# FPGA.net
KiCad netlist of a schematic drawn in Altium Designer
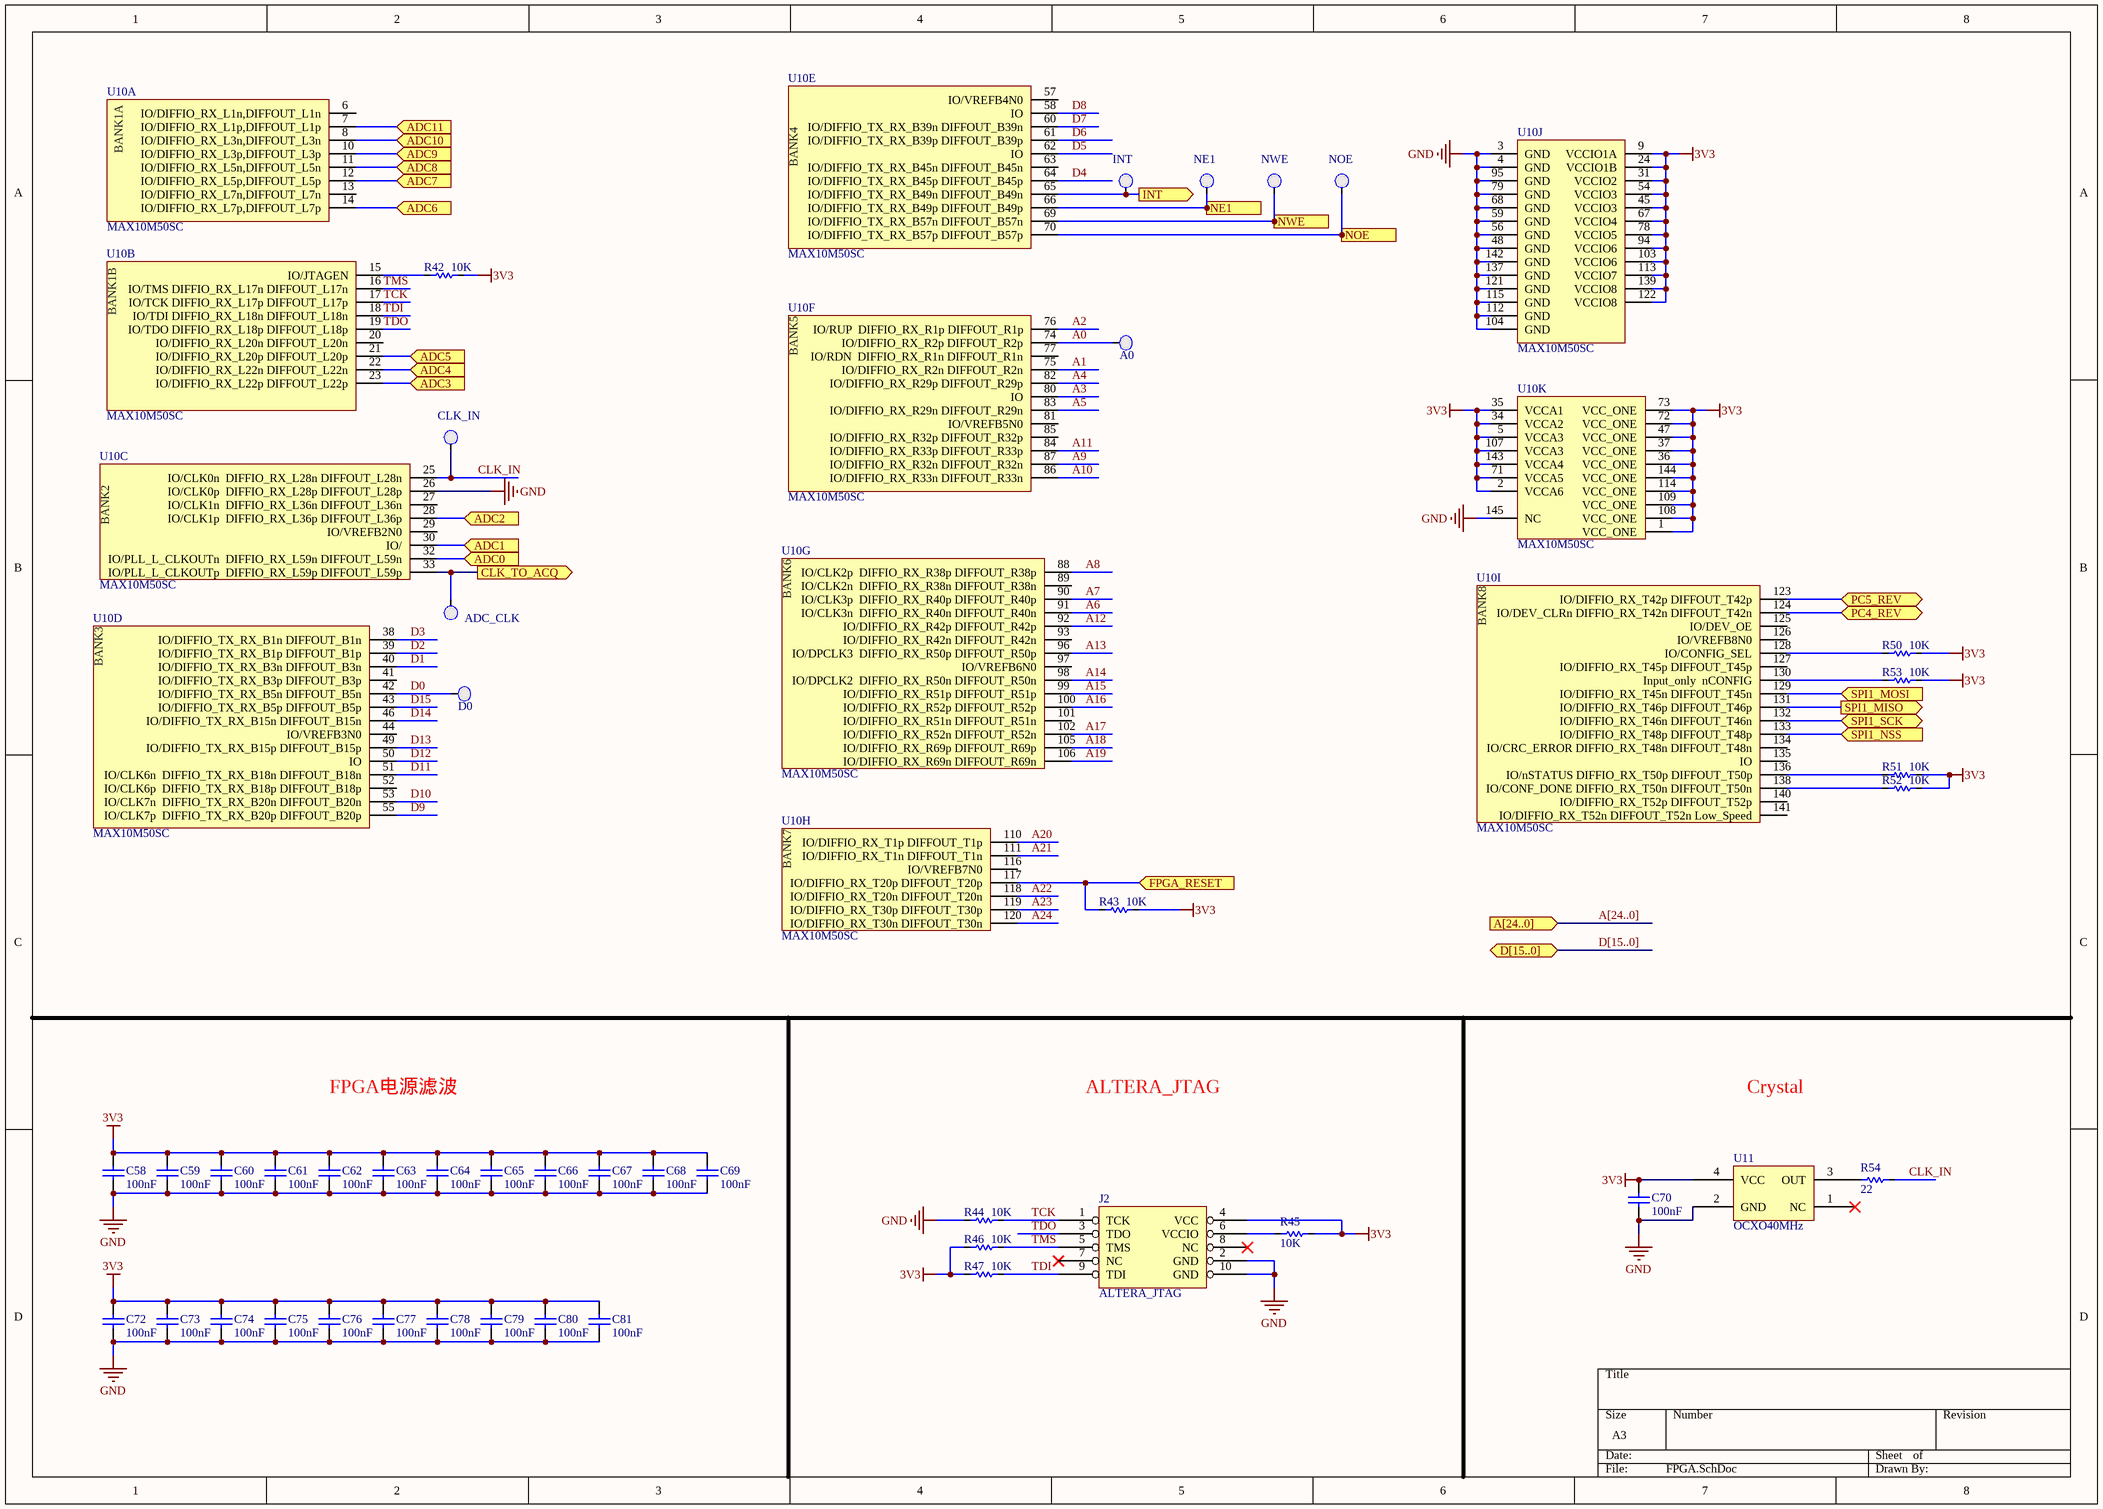
[diagram p0: FPGA.SchDoc]

(export (version "E")
  (design (tool "Eeschema 10.0.6"))
  (components
    (comp (ref "A0") (value "TP") (footprint "TPA") (libsource (lib "") (part "TP_1")))
    (comp (ref "ADC_CLK") (value "TP") (footprint "TPA") (libsource (lib "") (part "TP_2")))
    (comp (ref "C58")
      (value "100nF")
      (footprint "0805C")
      (description "Capacitor")
      (fields (field (name "PUBLISHER") "Altium Limited"))
      (libsource (lib "STM32") (part "Cap"))
    )
    (comp (ref "C59")
      (value "100nF")
      (footprint "0805C")
      (description "Capacitor")
      (fields (field (name "PUBLISHER") "Altium Limited"))
      (libsource (lib "STM32") (part "Cap"))
    )
    (comp (ref "C60")
      (value "100nF")
      (footprint "0805C")
      (description "Capacitor")
      (fields (field (name "PUBLISHER") "Altium Limited"))
      (libsource (lib "STM32") (part "Cap"))
    )
    (comp (ref "C61")
      (value "100nF")
      (footprint "0805C")
      (description "Capacitor")
      (fields (field (name "PUBLISHER") "Altium Limited"))
      (libsource (lib "STM32") (part "Cap"))
    )
    (comp (ref "C62")
      (value "100nF")
      (footprint "0805C")
      (description "Capacitor")
      (fields (field (name "PUBLISHER") "Altium Limited"))
      (libsource (lib "STM32") (part "Cap"))
    )
    (comp (ref "C63")
      (value "100nF")
      (footprint "0805C")
      (description "Capacitor")
      (fields (field (name "PUBLISHER") "Altium Limited"))
      (libsource (lib "STM32") (part "Cap"))
    )
    (comp (ref "C64")
      (value "100nF")
      (footprint "0805C")
      (description "Capacitor")
      (fields (field (name "PUBLISHER") "Altium Limited"))
      (libsource (lib "STM32") (part "Cap"))
    )
    (comp (ref "C65")
      (value "100nF")
      (footprint "0805C")
      (description "Capacitor")
      (fields (field (name "PUBLISHER") "Altium Limited"))
      (libsource (lib "STM32") (part "Cap"))
    )
    (comp (ref "C66")
      (value "100nF")
      (footprint "0805C")
      (description "Capacitor")
      (fields (field (name "PUBLISHER") "Altium Limited"))
      (libsource (lib "STM32") (part "Cap"))
    )
    (comp (ref "C67")
      (value "100nF")
      (footprint "0805C")
      (description "Capacitor")
      (fields (field (name "PUBLISHER") "Altium Limited"))
      (libsource (lib "STM32") (part "Cap"))
    )
    (comp (ref "C68")
      (value "100nF")
      (footprint "0805C")
      (description "Capacitor")
      (fields (field (name "PUBLISHER") "Altium Limited"))
      (libsource (lib "STM32") (part "Cap"))
    )
    (comp (ref "C69")
      (value "100nF")
      (footprint "0805C")
      (description "Capacitor")
      (fields (field (name "PUBLISHER") "Altium Limited"))
      (libsource (lib "STM32") (part "Cap"))
    )
    (comp (ref "C70")
      (value "100nF")
      (footprint "0805C")
      (description "Capacitor")
      (fields (field (name "PUBLISHER") "Altium Limited"))
      (libsource (lib "STM32") (part "Cap"))
    )
    (comp (ref "C72")
      (value "100nF")
      (footprint "0805C")
      (description "Capacitor")
      (fields (field (name "PUBLISHER") "Altium Limited"))
      (libsource (lib "STM32") (part "Cap"))
    )
    (comp (ref "C73")
      (value "100nF")
      (footprint "0805C")
      (description "Capacitor")
      (fields (field (name "PUBLISHER") "Altium Limited"))
      (libsource (lib "STM32") (part "Cap"))
    )
    (comp (ref "C74")
      (value "100nF")
      (footprint "0805C")
      (description "Capacitor")
      (fields (field (name "PUBLISHER") "Altium Limited"))
      (libsource (lib "STM32") (part "Cap"))
    )
    (comp (ref "C75")
      (value "100nF")
      (footprint "0805C")
      (description "Capacitor")
      (fields (field (name "PUBLISHER") "Altium Limited"))
      (libsource (lib "STM32") (part "Cap"))
    )
    (comp (ref "C76")
      (value "100nF")
      (footprint "0805C")
      (description "Capacitor")
      (fields (field (name "PUBLISHER") "Altium Limited"))
      (libsource (lib "STM32") (part "Cap"))
    )
    (comp (ref "C77")
      (value "100nF")
      (footprint "0805C")
      (description "Capacitor")
      (fields (field (name "PUBLISHER") "Altium Limited"))
      (libsource (lib "STM32") (part "Cap"))
    )
    (comp (ref "C78")
      (value "100nF")
      (footprint "0805C")
      (description "Capacitor")
      (fields (field (name "PUBLISHER") "Altium Limited"))
      (libsource (lib "STM32") (part "Cap"))
    )
    (comp (ref "C79")
      (value "100nF")
      (footprint "0805C")
      (description "Capacitor")
      (fields (field (name "PUBLISHER") "Altium Limited"))
      (libsource (lib "STM32") (part "Cap"))
    )
    (comp (ref "C80")
      (value "100nF")
      (footprint "0805C")
      (description "Capacitor")
      (fields (field (name "PUBLISHER") "Altium Limited"))
      (libsource (lib "STM32") (part "Cap"))
    )
    (comp (ref "C81")
      (value "100nF")
      (footprint "0805C")
      (description "Capacitor")
      (fields (field (name "PUBLISHER") "Altium Limited"))
      (libsource (lib "STM32") (part "Cap"))
    )
    (comp (ref "CLK_IN") (value "TP") (footprint "TPA") (libsource (lib "STM32") (part "TP")))
    (comp (ref "D0") (value "TP") (footprint "TPA") (libsource (lib "") (part "TP_1")))
    (comp (ref "INT") (value "TP") (footprint "TPA") (libsource (lib "STM32") (part "TP")))
    (comp (ref "J2")
      (value "ALTERA_JTAG")
      (footprint "JTAG_DIP")
      (libsource (lib "STM32") (part "ALTERA_JTAG"))
    )
    (comp (ref "NE1") (value "TP") (footprint "TPA") (libsource (lib "STM32") (part "TP")))
    (comp (ref "NOE") (value "TP") (footprint "TPA") (libsource (lib "STM32") (part "TP")))
    (comp (ref "NWE") (value "TP") (footprint "TPA") (libsource (lib "STM32") (part "TP")))
    (comp (ref "R42")
      (value "10K")
      (footprint "0805R")
      (description "Resistor")
      (fields (field (name "PUBLISHER") "Altium Limited"))
      (libsource (lib "STM32") (part "Res1"))
    )
    (comp (ref "R43")
      (value "10K")
      (footprint "0805R")
      (description "Resistor")
      (fields (field (name "PUBLISHER") "Altium Limited"))
      (libsource (lib "STM32") (part "Res1"))
    )
    (comp (ref "R44")
      (value "10K")
      (footprint "0805R")
      (description "Resistor")
      (fields (field (name "PUBLISHER") "Altium Limited"))
      (libsource (lib "STM32") (part "Res1"))
    )
    (comp (ref "R45")
      (value "10K")
      (footprint "0805R")
      (description "Resistor")
      (fields (field (name "PUBLISHER") "Altium Limited"))
      (libsource (lib "STM32") (part "Res1"))
    )
    (comp (ref "R46")
      (value "10K")
      (footprint "0805R")
      (description "Resistor")
      (fields (field (name "PUBLISHER") "Altium Limited"))
      (libsource (lib "STM32") (part "Res1"))
    )
    (comp (ref "R47")
      (value "10K")
      (footprint "0805R")
      (description "Resistor")
      (fields (field (name "PUBLISHER") "Altium Limited"))
      (libsource (lib "STM32") (part "Res1"))
    )
    (comp (ref "R50")
      (value "10K")
      (footprint "0805R")
      (description "Resistor")
      (fields (field (name "PUBLISHER") "Altium Limited"))
      (libsource (lib "STM32") (part "Res1"))
    )
    (comp (ref "R51")
      (value "10K")
      (footprint "0805R")
      (description "Resistor")
      (fields (field (name "PUBLISHER") "Altium Limited"))
      (libsource (lib "STM32") (part "Res1"))
    )
    (comp (ref "R52")
      (value "10K")
      (footprint "0805R")
      (description "Resistor")
      (fields (field (name "PUBLISHER") "Altium Limited"))
      (libsource (lib "STM32") (part "Res1"))
    )
    (comp (ref "R53")
      (value "10K")
      (footprint "0805R")
      (description "Resistor")
      (fields (field (name "PUBLISHER") "Altium Limited"))
      (libsource (lib "STM32") (part "Res1"))
    )
    (comp (ref "R54")
      (value "22")
      (footprint "0805R")
      (description "Resistor")
      (fields (field (name "PUBLISHER") "Altium Limited"))
      (libsource (lib "STM32") (part "Res1"))
    )
    (comp (ref "U10")
      (value "MAX10M50SC")
      (footprint "max10M50sc_Quad144")
      (libsource (lib "STM32") (part "MAX10M50SC_144"))
    )
    (comp (ref "U11") (value "OCXO40MHz") (footprint "OCX1") (libsource (lib "STM32") (part "OCXO")))
  )
  (nets
    (net (code "1") (name "/A0") (class "Default")
      (node (ref "A0") (pin "1") (pinfunction "TP_1") (pintype "passive"))
      (node (ref "U10") (pin "74") (pinfunction "IO/DIFFIO_RX_R2p_DIFFOUT_R2p_74") (pintype "passive"))
    )
    (net (code "2") (name "/A1") (class "Default")
      (node (ref "U10") (pin "75") (pinfunction "IO/DIFFIO_RX_R2n_DIFFOUT_R2n_75") (pintype "passive"))
    )
    (net (code "3") (name "/A2") (class "Default")
      (node (ref "U10") (pin "76") (pinfunction "IO/RUP__DIFFIO_RX_R1p_DIFFOUT_R1p_76") (pintype "passive"))
    )
    (net (code "4") (name "/A3") (class "Default")
      (node (ref "U10") (pin "80") (pinfunction "IO_80") (pintype "passive"))
    )
    (net (code "5") (name "/A4") (class "Default")
      (node (ref "U10") (pin "82") (pinfunction "IO/DIFFIO_RX_R29p_DIFFOUT_R29p_82") (pintype "passive"))
    )
    (net (code "6") (name "/A5") (class "Default")
      (node (ref "U10") (pin "83") (pinfunction "IO/DIFFIO_RX_R29n_DIFFOUT_R29n_83") (pintype "passive"))
    )
    (net (code "7") (name "/A6") (class "Default")
      (node (ref "U10") (pin "91") (pinfunction "IO/CLK3n__DIFFIO_RX_R40n_DIFFOUT_R40n_91") (pintype "passive"))
    )
    (net (code "8") (name "/A7") (class "Default")
      (node (ref "U10") (pin "90") (pinfunction "IO/CLK3p__DIFFIO_RX_R40p_DIFFOUT_R40p_90") (pintype "passive"))
    )
    (net (code "9") (name "/A8") (class "Default")
      (node (ref "U10") (pin "88") (pinfunction "IO/CLK2p__DIFFIO_RX_R38p_DIFFOUT_R38p_88") (pintype "passive"))
    )
    (net (code "10") (name "/A9") (class "Default")
      (node (ref "U10") (pin "87") (pinfunction "IO/DIFFIO_RX_R32n_DIFFOUT_R32n_87") (pintype "passive"))
    )
    (net (code "11") (name "/A10") (class "Default")
      (node (ref "U10") (pin "86") (pinfunction "IO/DIFFIO_RX_R33n_DIFFOUT_R33n_86") (pintype "passive"))
    )
    (net (code "12") (name "/A11") (class "Default")
      (node (ref "U10") (pin "84") (pinfunction "IO/DIFFIO_RX_R33p_DIFFOUT_R33p_84") (pintype "passive"))
    )
    (net (code "13") (name "/A12") (class "Default")
      (node (ref "U10") (pin "92") (pinfunction "IO/DIFFIO_RX_R42p_DIFFOUT_R42p_92") (pintype "passive"))
    )
    (net (code "14") (name "/A13") (class "Default")
      (node (ref "U10") (pin "96") (pinfunction "IO/DPCLK3__DIFFIO_RX_R50p_DIFFOUT_R50p_96") (pintype "passive"))
    )
    (net (code "15") (name "/A14") (class "Default")
      (node (ref "U10") (pin "98") (pinfunction "IO/DPCLK2__DIFFIO_RX_R50n_DIFFOUT_R50n_98") (pintype "passive"))
    )
    (net (code "16") (name "/A15") (class "Default")
      (node (ref "U10") (pin "99") (pinfunction "IO/DIFFIO_RX_R51p_DIFFOUT_R51p_99") (pintype "passive"))
    )
    (net (code "17") (name "/A16") (class "Default")
      (node (ref "U10") (pin "100") (pinfunction "IO/DIFFIO_RX_R52p_DIFFOUT_R52p_100") (pintype "passive"))
    )
    (net (code "18") (name "/A17") (class "Default")
      (node (ref "U10") (pin "102") (pinfunction "IO/DIFFIO_RX_R52n_DIFFOUT_R52n_102") (pintype "passive"))
    )
    (net (code "19") (name "/A18") (class "Default")
      (node (ref "U10") (pin "105") (pinfunction "IO/DIFFIO_RX_R69p_DIFFOUT_R69p_105") (pintype "passive"))
    )
    (net (code "20") (name "/A19") (class "Default")
      (node (ref "U10") (pin "106") (pinfunction "IO/DIFFIO_RX_R69n_DIFFOUT_R69n_106") (pintype "passive"))
    )
    (net (code "21") (name "/A20") (class "Default")
      (node (ref "U10") (pin "110") (pinfunction "IO/DIFFIO_RX_T1p_DIFFOUT_T1p_110") (pintype "passive"))
    )
    (net (code "22") (name "/A21") (class "Default")
      (node (ref "U10") (pin "111") (pinfunction "IO/DIFFIO_RX_T1n_DIFFOUT_T1n_111") (pintype "passive"))
    )
    (net (code "23") (name "/A22") (class "Default")
      (node (ref "U10") (pin "118") (pinfunction "IO/DIFFIO_RX_T20n_DIFFOUT_T20n_118") (pintype "passive"))
    )
    (net (code "24") (name "/A23") (class "Default")
      (node (ref "U10") (pin "119") (pinfunction "IO/DIFFIO_RX_T30p_DIFFOUT_T30p_119") (pintype "passive"))
    )
    (net (code "25") (name "/A24") (class "Default")
      (node (ref "U10") (pin "120") (pinfunction "IO/DIFFIO_RX_T30n_DIFFOUT_T30n_120") (pintype "passive"))
    )
    (net (code "26") (name "/ADC0") (class "Default")
      (node (ref "U10") (pin "32") (pinfunction "IO/PLL_L_CLKOUTn__DIFFIO_RX_L59n_DIFFOUT_L59n_32") (pintype "passive"))
    )
    (net (code "27") (name "/ADC1") (class "Default")
      (node (ref "U10") (pin "30") (pinfunction "IO/_30") (pintype "passive"))
    )
    (net (code "28") (name "/ADC2") (class "Default")
      (node (ref "U10") (pin "28") (pinfunction "IO/CLK1p__DIFFIO_RX_L36p_DIFFOUT_L36p_28") (pintype "passive"))
    )
    (net (code "29") (name "/ADC3") (class "Default")
      (node (ref "U10") (pin "23") (pinfunction "IO/DIFFIO_RX_L22p_DIFFOUT_L22p_23") (pintype "passive"))
    )
    (net (code "30") (name "/ADC4") (class "Default")
      (node (ref "U10") (pin "22") (pinfunction "IO/DIFFIO_RX_L22n_DIFFOUT_L22n_22") (pintype "passive"))
    )
    (net (code "31") (name "/ADC5") (class "Default")
      (node (ref "U10") (pin "21") (pinfunction "IO/DIFFIO_RX_L20p_DIFFOUT_L20p_21") (pintype "passive"))
    )
    (net (code "32") (name "/ADC6") (class "Default")
      (node (ref "U10") (pin "14") (pinfunction "IO/DIFFIO_RX_L7p,DIFFOUT_L7p_14") (pintype "passive"))
    )
    (net (code "33") (name "/ADC7") (class "Default")
      (node (ref "U10") (pin "12") (pinfunction "IO/DIFFIO_RX_L5p,DIFFOUT_L5p_12") (pintype "passive"))
    )
    (net (code "34") (name "/ADC8") (class "Default")
      (node (ref "U10") (pin "11") (pinfunction "IO/DIFFIO_RX_L5n,DIFFOUT_L5n_11") (pintype "passive"))
    )
    (net (code "35") (name "/ADC9") (class "Default")
      (node (ref "U10") (pin "10") (pinfunction "IO/DIFFIO_RX_L3p,DIFFOUT_L3p_10") (pintype "passive"))
    )
    (net (code "36") (name "/ADC10") (class "Default")
      (node (ref "U10") (pin "8") (pinfunction "IO/DIFFIO_RX_L3n,DIFFOUT_L3n_8") (pintype "passive"))
    )
    (net (code "37") (name "/ADC11") (class "Default")
      (node (ref "U10") (pin "7") (pinfunction "IO/DIFFIO_RX_L1p,DIFFOUT_L1p_7") (pintype "passive"))
    )
    (net (code "39") (name "/CLK_IN") (class "Default")
      (node (ref "CLK_IN") (pin "1") (pinfunction "TP_1") (pintype "passive"))
      (node (ref "R54") (pin "2") (pinfunction "2_2") (pintype "passive"))
      (node (ref "U10") (pin "25") (pinfunction "IO/CLK0n__DIFFIO_RX_L28n_DIFFOUT_L28n_25") (pintype "passive"))
    )
    (net (code "40") (name "/CLK_TO_ACQ") (class "Default")
      (node (ref "ADC_CLK") (pin "1") (pinfunction "TP_1") (pintype "passive"))
      (node (ref "U10") (pin "33") (pinfunction "IO/PLL_L_CLKOUTp__DIFFIO_RX_L59p_DIFFOUT_L59p_33") (pintype "passive"))
    )
    (net (code "41") (name "/D0") (class "Default")
      (node (ref "D0") (pin "1") (pinfunction "TP_1") (pintype "passive"))
      (node (ref "U10") (pin "42") (pinfunction "IO/DIFFIO_TX_RX_B5n_DIFFOUT_B5n_42") (pintype "passive"))
    )
    (net (code "42") (name "/D1") (class "Default")
      (node (ref "U10") (pin "40") (pinfunction "IO/DIFFIO_TX_RX_B3n_DIFFOUT_B3n_40") (pintype "passive"))
    )
    (net (code "43") (name "/D2") (class "Default")
      (node (ref "U10") (pin "39") (pinfunction "IO/DIFFIO_TX_RX_B1p_DIFFOUT_B1p_39") (pintype "passive"))
    )
    (net (code "44") (name "/D3") (class "Default")
      (node (ref "U10") (pin "38") (pinfunction "IO/DIFFIO_TX_RX_B1n_DIFFOUT_B1n_38") (pintype "passive"))
    )
    (net (code "45") (name "/D4") (class "Default")
      (node (ref "U10") (pin "64") (pinfunction "IO/DIFFIO_TX_RX_B45p_DIFFOUT_B45p_64") (pintype "passive"))
    )
    (net (code "46") (name "/D5") (class "Default")
      (node (ref "U10") (pin "62") (pinfunction "IO_62") (pintype "passive"))
    )
    (net (code "47") (name "/D6") (class "Default")
      (node (ref "U10") (pin "61") (pinfunction "IO/DIFFIO_TX_RX_B39p_DIFFOUT_B39p_61") (pintype "passive"))
    )
    (net (code "48") (name "/D7") (class "Default")
      (node (ref "U10") (pin "60") (pinfunction "IO/DIFFIO_TX_RX_B39n_DIFFOUT_B39n_60") (pintype "passive"))
    )
    (net (code "49") (name "/D8") (class "Default")
      (node (ref "U10") (pin "58") (pinfunction "IO_58") (pintype "passive"))
    )
    (net (code "50") (name "/D9") (class "Default")
      (node (ref "U10") (pin "55") (pinfunction "IO/CLK7p__DIFFIO_TX_RX_B20p_DIFFOUT_B20p_55") (pintype "passive"))
    )
    (net (code "51") (name "/D10") (class "Default")
      (node (ref "U10") (pin "53") (pinfunction "IO/CLK7n__DIFFIO_TX_RX_B20n_DIFFOUT_B20n_53") (pintype "passive"))
    )
    (net (code "52") (name "/D11") (class "Default")
      (node (ref "U10") (pin "51") (pinfunction "IO/CLK6n__DIFFIO_TX_RX_B18n_DIFFOUT_B18n_51") (pintype "passive"))
    )
    (net (code "53") (name "/D12") (class "Default")
      (node (ref "U10") (pin "50") (pinfunction "IO_50") (pintype "passive"))
    )
    (net (code "54") (name "/D13") (class "Default")
      (node (ref "U10") (pin "49") (pinfunction "IO/DIFFIO_TX_RX_B15p_DIFFOUT_B15p_49") (pintype "passive"))
    )
    (net (code "55") (name "/D14") (class "Default")
      (node (ref "U10") (pin "46") (pinfunction "IO/DIFFIO_TX_RX_B15n_DIFFOUT_B15n_46") (pintype "passive"))
    )
    (net (code "56") (name "/D15") (class "Default")
      (node (ref "U10") (pin "43") (pinfunction "IO/DIFFIO_TX_RX_B5p_DIFFOUT_B5p_43") (pintype "passive"))
    )
    (net (code "58") (name "/FPGA_RESET") (class "Default")
      (node (ref "R43") (pin "1") (pinfunction "1_1") (pintype "passive"))
      (node (ref "U10") (pin "117") (pinfunction "IO/DIFFIO_RX_T20p_DIFFOUT_T20p_117") (pintype "passive"))
    )
    (net (code "59") (name "/INT") (class "Default")
      (node (ref "INT") (pin "1") (pinfunction "TP_1") (pintype "passive"))
      (node (ref "U10") (pin "65") (pinfunction "IO/DIFFIO_TX_RX_B49n_DIFFOUT_B49n_65") (pintype "passive"))
    )
    (net (code "60") (name "/NE1") (class "Default")
      (node (ref "NE1") (pin "1") (pinfunction "TP_1") (pintype "passive"))
      (node (ref "U10") (pin "66") (pinfunction "IO/DIFFIO_TX_RX_B49p_DIFFOUT_B49p_66") (pintype "passive"))
    )
    (net (code "61") (name "/NOE") (class "Default")
      (node (ref "NOE") (pin "1") (pinfunction "TP_1") (pintype "passive"))
      (node (ref "U10") (pin "70") (pinfunction "IO/DIFFIO_TX_RX_B57p_DIFFOUT_B57p_70") (pintype "passive"))
    )
    (net (code "62") (name "/NWE") (class "Default")
      (node (ref "NWE") (pin "1") (pinfunction "TP_1") (pintype "passive"))
      (node (ref "U10") (pin "69") (pinfunction "IO/DIFFIO_TX_RX_B57n_DIFFOUT_B57n_69") (pintype "passive"))
    )
    (net (code "63") (name "/PC4_REV") (class "Default")
      (node (ref "U10") (pin "124") (pinfunction "IO/DEV_CLRn_DIFFIO_RX_T42n_DIFFOUT_T42n_124") (pintype "passive"))
    )
    (net (code "64") (name "/PC5_REV") (class "Default")
      (node (ref "U10") (pin "123") (pinfunction "IO/DIFFIO_RX_T42p_DIFFOUT_T42p_123") (pintype "passive"))
    )
    (net (code "65") (name "/SPI1_MISO") (class "Default")
      (node (ref "U10") (pin "131") (pinfunction "IO/DIFFIO_RX_T46p_DIFFOUT_T46p_131") (pintype "passive"))
    )
    (net (code "66") (name "/SPI1_MOSI") (class "Default")
      (node (ref "U10") (pin "129") (pinfunction "IO/DIFFIO_RX_T45n_DIFFOUT_T45n_129") (pintype "passive"))
    )
    (net (code "67") (name "/SPI1_NSS") (class "Default")
      (node (ref "U10") (pin "133") (pinfunction "IO/DIFFIO_RX_T48p_DIFFOUT_T48p_133") (pintype "passive"))
    )
    (net (code "68") (name "/SPI1_SCK") (class "Default")
      (node (ref "U10") (pin "132") (pinfunction "IO/DIFFIO_RX_T46n_DIFFOUT_T46n_132") (pintype "passive"))
    )
    (net (code "69") (name "/TCK") (class "Default")
      (node (ref "J2") (pin "1") (pinfunction "TCK_1") (pintype "passive"))
      (node (ref "R44") (pin "2") (pinfunction "2_2") (pintype "passive"))
      (node (ref "U10") (pin "17") (pinfunction "IO/TCK_DIFFIO_RX_L17p_DIFFOUT_L17p_17") (pintype "passive"))
    )
    (net (code "70") (name "/TDI") (class "Default")
      (node (ref "J2") (pin "9") (pinfunction "TDI_9") (pintype "passive"))
      (node (ref "R47") (pin "2") (pinfunction "2_2") (pintype "passive"))
      (node (ref "U10") (pin "18") (pinfunction "IO/TDI_DIFFIO_RX_L18n_DIFFOUT_L18n_18") (pintype "passive"))
    )
    (net (code "71") (name "/TDO") (class "Default")
      (node (ref "J2") (pin "3") (pinfunction "TDO_3") (pintype "passive"))
      (node (ref "U10") (pin "19") (pinfunction "IO/TDO_DIFFIO_RX_L18p_DIFFOUT_L18p_19") (pintype "passive"))
    )
    (net (code "72") (name "/TMS") (class "Default")
      (node (ref "J2") (pin "5") (pinfunction "TMS_5") (pintype "passive"))
      (node (ref "R46") (pin "2") (pinfunction "2_2") (pintype "passive"))
      (node (ref "U10") (pin "16") (pinfunction "IO/TMS_DIFFIO_RX_L17n_DIFFOUT_L17n_16") (pintype "passive"))
    )
    (net (code "73") (name "3V3") (class "Default")
      (node (ref "C58") (pin "2") (pinfunction "2_2") (pintype "passive"))
      (node (ref "C59") (pin "2") (pinfunction "2_2") (pintype "passive"))
      (node (ref "C60") (pin "2") (pinfunction "2_2") (pintype "passive"))
      (node (ref "C61") (pin "2") (pinfunction "2_2") (pintype "passive"))
      (node (ref "C62") (pin "2") (pinfunction "2_2") (pintype "passive"))
      (node (ref "C63") (pin "2") (pinfunction "2_2") (pintype "passive"))
      (node (ref "C64") (pin "2") (pinfunction "2_2") (pintype "passive"))
      (node (ref "C65") (pin "2") (pinfunction "2_2") (pintype "passive"))
      (node (ref "C66") (pin "2") (pinfunction "2_2") (pintype "passive"))
      (node (ref "C67") (pin "2") (pinfunction "2_2") (pintype "passive"))
      (node (ref "C68") (pin "2") (pinfunction "2_2") (pintype "passive"))
      (node (ref "C69") (pin "2") (pinfunction "2_2") (pintype "passive"))
      (node (ref "C70") (pin "2") (pinfunction "2_2") (pintype "passive"))
      (node (ref "C72") (pin "2") (pinfunction "2_2") (pintype "passive"))
      (node (ref "C73") (pin "2") (pinfunction "2_2") (pintype "passive"))
      (node (ref "C74") (pin "2") (pinfunction "2_2") (pintype "passive"))
      (node (ref "C75") (pin "2") (pinfunction "2_2") (pintype "passive"))
      (node (ref "C76") (pin "2") (pinfunction "2_2") (pintype "passive"))
      (node (ref "C77") (pin "2") (pinfunction "2_2") (pintype "passive"))
      (node (ref "C78") (pin "2") (pinfunction "2_2") (pintype "passive"))
      (node (ref "C79") (pin "2") (pinfunction "2_2") (pintype "passive"))
      (node (ref "C80") (pin "2") (pinfunction "2_2") (pintype "passive"))
      (node (ref "C81") (pin "2") (pinfunction "2_2") (pintype "passive"))
      (node (ref "J2") (pin "4") (pinfunction "VCC_4") (pintype "passive"))
      (node (ref "R42") (pin "2") (pinfunction "2_2") (pintype "passive"))
      (node (ref "R43") (pin "2") (pinfunction "2_2") (pintype "passive"))
      (node (ref "R45") (pin "2") (pinfunction "2_2") (pintype "passive"))
      (node (ref "R46") (pin "1") (pinfunction "1_1") (pintype "passive"))
      (node (ref "R47") (pin "1") (pinfunction "1_1") (pintype "passive"))
      (node (ref "R50") (pin "2") (pinfunction "2_2") (pintype "passive"))
      (node (ref "R51") (pin "2") (pinfunction "2_2") (pintype "passive"))
      (node (ref "R52") (pin "2") (pinfunction "2_2") (pintype "passive"))
      (node (ref "R53") (pin "2") (pinfunction "2_2") (pintype "passive"))
      (node (ref "U10") (pin "1") (pinfunction "VCC_ONE_1") (pintype "passive"))
      (node (ref "U10") (pin "103") (pinfunction "VCCIO6_103") (pintype "passive"))
      (node (ref "U10") (pin "107") (pinfunction "VCCA3_107") (pintype "passive"))
      (node (ref "U10") (pin "108") (pinfunction "VCC_ONE_108") (pintype "passive"))
      (node (ref "U10") (pin "109") (pinfunction "VCC_ONE_109") (pintype "passive"))
      (node (ref "U10") (pin "113") (pinfunction "VCCIO7_113") (pintype "passive"))
      (node (ref "U10") (pin "114") (pinfunction "VCC_ONE_114") (pintype "passive"))
      (node (ref "U10") (pin "122") (pinfunction "VCCIO8_122") (pintype "passive"))
      (node (ref "U10") (pin "139") (pinfunction "VCCIO8_139") (pintype "passive"))
      (node (ref "U10") (pin "143") (pinfunction "VCCA4_143") (pintype "passive"))
      (node (ref "U10") (pin "144") (pinfunction "VCC_ONE_144") (pintype "passive"))
      (node (ref "U10") (pin "2") (pinfunction "VCCA6_2") (pintype "passive"))
      (node (ref "U10") (pin "24") (pinfunction "VCCIO1B_24") (pintype "passive"))
      (node (ref "U10") (pin "31") (pinfunction "VCCIO2_31") (pintype "passive"))
      (node (ref "U10") (pin "34") (pinfunction "VCCA2_34") (pintype "passive"))
      (node (ref "U10") (pin "35") (pinfunction "VCCA1_35") (pintype "passive"))
      (node (ref "U10") (pin "36") (pinfunction "VCC_ONE_36") (pintype "passive"))
      (node (ref "U10") (pin "37") (pinfunction "VCC_ONE_37") (pintype "passive"))
      (node (ref "U10") (pin "45") (pinfunction "VCCIO3_45") (pintype "passive"))
      (node (ref "U10") (pin "47") (pinfunction "VCC_ONE_47") (pintype "passive"))
      (node (ref "U10") (pin "5") (pinfunction "VCCA3_5") (pintype "passive"))
      (node (ref "U10") (pin "54") (pinfunction "VCCIO3_54") (pintype "passive"))
      (node (ref "U10") (pin "67") (pinfunction "VCCIO4_67") (pintype "passive"))
      (node (ref "U10") (pin "71") (pinfunction "VCCA5_71") (pintype "passive"))
      (node (ref "U10") (pin "72") (pinfunction "VCC_ONE_72") (pintype "passive"))
      (node (ref "U10") (pin "73") (pinfunction "VCC_ONE_73") (pintype "passive"))
      (node (ref "U10") (pin "78") (pinfunction "VCCIO5_78") (pintype "passive"))
      (node (ref "U10") (pin "9") (pinfunction "VCCIO1A_9") (pintype "passive"))
      (node (ref "U10") (pin "94") (pinfunction "VCCIO6_94") (pintype "passive"))
      (node (ref "U11") (pin "4") (pinfunction "VCC_4") (pintype "passive"))
    )
    (net (code "74") (name "GND") (class "Default")
      (node (ref "C58") (pin "1") (pinfunction "1_1") (pintype "passive"))
      (node (ref "C59") (pin "1") (pinfunction "1_1") (pintype "passive"))
      (node (ref "C60") (pin "1") (pinfunction "1_1") (pintype "passive"))
      (node (ref "C61") (pin "1") (pinfunction "1_1") (pintype "passive"))
      (node (ref "C62") (pin "1") (pinfunction "1_1") (pintype "passive"))
      (node (ref "C63") (pin "1") (pinfunction "1_1") (pintype "passive"))
      (node (ref "C64") (pin "1") (pinfunction "1_1") (pintype "passive"))
      (node (ref "C65") (pin "1") (pinfunction "1_1") (pintype "passive"))
      (node (ref "C66") (pin "1") (pinfunction "1_1") (pintype "passive"))
      (node (ref "C67") (pin "1") (pinfunction "1_1") (pintype "passive"))
      (node (ref "C68") (pin "1") (pinfunction "1_1") (pintype "passive"))
      (node (ref "C69") (pin "1") (pinfunction "1_1") (pintype "passive"))
      (node (ref "C70") (pin "1") (pinfunction "1_1") (pintype "passive"))
      (node (ref "C72") (pin "1") (pinfunction "1_1") (pintype "passive"))
      (node (ref "C73") (pin "1") (pinfunction "1_1") (pintype "passive"))
      (node (ref "C74") (pin "1") (pinfunction "1_1") (pintype "passive"))
      (node (ref "C75") (pin "1") (pinfunction "1_1") (pintype "passive"))
      (node (ref "C76") (pin "1") (pinfunction "1_1") (pintype "passive"))
      (node (ref "C77") (pin "1") (pinfunction "1_1") (pintype "passive"))
      (node (ref "C78") (pin "1") (pinfunction "1_1") (pintype "passive"))
      (node (ref "C79") (pin "1") (pinfunction "1_1") (pintype "passive"))
      (node (ref "C80") (pin "1") (pinfunction "1_1") (pintype "passive"))
      (node (ref "C81") (pin "1") (pinfunction "1_1") (pintype "passive"))
      (node (ref "J2") (pin "10") (pinfunction "GND_10") (pintype "passive"))
      (node (ref "J2") (pin "2") (pinfunction "GND_2") (pintype "passive"))
      (node (ref "R44") (pin "1") (pinfunction "1_1") (pintype "passive"))
      (node (ref "U10") (pin "104") (pinfunction "GND_104") (pintype "passive"))
      (node (ref "U10") (pin "112") (pinfunction "GND_112") (pintype "passive"))
      (node (ref "U10") (pin "115") (pinfunction "GND_115") (pintype "passive"))
      (node (ref "U10") (pin "121") (pinfunction "GND_121") (pintype "passive"))
      (node (ref "U10") (pin "137") (pinfunction "GND_137") (pintype "passive"))
      (node (ref "U10") (pin "142") (pinfunction "GND_142") (pintype "passive"))
      (node (ref "U10") (pin "145") (pinfunction "NC_145") (pintype "passive"))
      (node (ref "U10") (pin "26") (pinfunction "IO/CLK0p__DIFFIO_RX_L28p_DIFFOUT_L28p_26") (pintype "passive"))
      (node (ref "U10") (pin "3") (pinfunction "GND_3") (pintype "passive"))
      (node (ref "U10") (pin "4") (pinfunction "GND_4") (pintype "passive"))
      (node (ref "U10") (pin "48") (pinfunction "GND_48") (pintype "passive"))
      (node (ref "U10") (pin "56") (pinfunction "GND_56") (pintype "passive"))
      (node (ref "U10") (pin "59") (pinfunction "GND_59") (pintype "passive"))
      (node (ref "U10") (pin "68") (pinfunction "GND_68") (pintype "passive"))
      (node (ref "U10") (pin "79") (pinfunction "GND_79") (pintype "passive"))
      (node (ref "U10") (pin "95") (pinfunction "GND_95") (pintype "passive"))
      (node (ref "U11") (pin "2") (pinfunction "GND_2") (pintype "passive"))
    )
    (net (code "75") (name "Net-(J2-VCCIO)") (class "Default")
      (node (ref "J2") (pin "6") (pinfunction "VCCIO_6") (pintype "passive"))
      (node (ref "R45") (pin "1") (pinfunction "1_1") (pintype "passive"))
    )
    (net (code "76") (name "Net-(U10B-IO{slash}JTAGEN)") (class "Default")
      (node (ref "R42") (pin "1") (pinfunction "1_1") (pintype "passive"))
      (node (ref "U10") (pin "15") (pinfunction "IO/JTAGEN_15") (pintype "passive"))
    )
    (net (code "77") (name "Net-(U10I-IO{slash}CONFIG_SEL)") (class "Default")
      (node (ref "R50") (pin "1") (pinfunction "1_1") (pintype "passive"))
      (node (ref "U10") (pin "128") (pinfunction "IO/CONFIG_SEL_128") (pintype "passive"))
    )
    (net (code "78") (name "Net-(U10I-IO{slash}CONF_DONE_DIFFIO_RX_T50n_DIFFOUT_T50n)") (class "Default")
      (node (ref "R52") (pin "1") (pinfunction "1_1") (pintype "passive"))
      (node (ref "U10") (pin "138") (pinfunction "IO/CONF_DONE_DIFFIO_RX_T50n_DIFFOUT_T50n_138") (pintype "passive"))
    )
    (net (code "79") (name "Net-(U10I-IO{slash}nSTATUS_DIFFIO_RX_T50p_DIFFOUT_T50p)") (class "Default")
      (node (ref "R51") (pin "1") (pinfunction "1_1") (pintype "passive"))
      (node (ref "U10") (pin "136") (pinfunction "IO/nSTATUS_DIFFIO_RX_T50p_DIFFOUT_T50p_136") (pintype "passive"))
    )
    (net (code "80") (name "Net-(U10I-Input_only__nCONFIG)") (class "Default")
      (node (ref "R53") (pin "1") (pinfunction "1_1") (pintype "passive"))
      (node (ref "U10") (pin "130") (pinfunction "Input_only__nCONFIG_130") (pintype "passive"))
    )
    (net (code "81") (name "Net-(U11-OUT)") (class "Default")
      (node (ref "R54") (pin "1") (pinfunction "1_1") (pintype "passive"))
      (node (ref "U11") (pin "3") (pinfunction "OUT_3") (pintype "passive"))
    )
    (net (code "82") (name "unconnected-(J2-NC-Pad7)") (class "Default")
      (node (ref "J2") (pin "7") (pinfunction "NC_7") (pintype "passive+no_connect"))
    )
    (net (code "83") (name "unconnected-(J2-NC-Pad8)") (class "Default")
      (node (ref "J2") (pin "8") (pinfunction "NC_8") (pintype "passive+no_connect"))
    )
    (net (code "84") (name "unconnected-(U10A-IO{slash}DIFFIO_RX_L1n,DIFFOUT_L1n-Pad6)") (class "Default")
      (node (ref "U10") (pin "6") (pinfunction "IO/DIFFIO_RX_L1n,DIFFOUT_L1n_6") (pintype "passive"))
    )
    (net (code "85") (name "unconnected-(U10A-IO{slash}DIFFIO_RX_L7n,DIFFOUT_L7n-Pad13)") (class "Default")
      (node (ref "U10") (pin "13") (pinfunction "IO/DIFFIO_RX_L7n,DIFFOUT_L7n_13") (pintype "passive"))
    )
    (net (code "86") (name "unconnected-(U10B-IO{slash}DIFFIO_RX_L20n_DIFFOUT_L20n-Pad20)") (class "Default")
      (node (ref "U10") (pin "20") (pinfunction "IO/DIFFIO_RX_L20n_DIFFOUT_L20n_20") (pintype "passive"))
    )
    (net (code "87") (name "unconnected-(U10C-IO{slash}CLK1n__DIFFIO_RX_L36n_DIFFOUT_L36n-Pad27)") (class "Default")
      (node (ref "U10") (pin "27") (pinfunction "IO/CLK1n__DIFFIO_RX_L36n_DIFFOUT_L36n_27") (pintype "passive"))
    )
    (net (code "88") (name "unconnected-(U10C-IO{slash}VREFB2N0-Pad29)") (class "Default")
      (node (ref "U10") (pin "29") (pinfunction "IO/VREFB2N0_29") (pintype "passive"))
    )
    (net (code "89") (name "unconnected-(U10D-IO{slash}CLK6p__DIFFIO_TX_RX_B18p_DIFFOUT_B18p-Pad52)") (class "Default")
      (node (ref "U10") (pin "52") (pinfunction "IO/CLK6p__DIFFIO_TX_RX_B18p_DIFFOUT_B18p_52") (pintype "passive"))
    )
    (net (code "90") (name "unconnected-(U10D-IO{slash}DIFFIO_TX_RX_B3p_DIFFOUT_B3p-Pad41)") (class "Default")
      (node (ref "U10") (pin "41") (pinfunction "IO/DIFFIO_TX_RX_B3p_DIFFOUT_B3p_41") (pintype "passive"))
    )
    (net (code "91") (name "unconnected-(U10D-IO{slash}VREFB3N0-Pad44)") (class "Default")
      (node (ref "U10") (pin "44") (pinfunction "IO/VREFB3N0_44") (pintype "passive"))
    )
    (net (code "92") (name "unconnected-(U10E-IO{slash}DIFFIO_TX_RX_B45n_DIFFOUT_B45n-Pad63)") (class "Default")
      (node (ref "U10") (pin "63") (pinfunction "IO/DIFFIO_TX_RX_B45n_DIFFOUT_B45n_63") (pintype "passive"))
    )
    (net (code "93") (name "unconnected-(U10E-IO{slash}VREFB4N0-Pad57)") (class "Default")
      (node (ref "U10") (pin "57") (pinfunction "IO/VREFB4N0_57") (pintype "passive"))
    )
    (net (code "94") (name "unconnected-(U10F-IO{slash}DIFFIO_RX_R32p_DIFFOUT_R32p-Pad85)") (class "Default")
      (node (ref "U10") (pin "85") (pinfunction "IO/DIFFIO_RX_R32p_DIFFOUT_R32p_85") (pintype "passive"))
    )
    (net (code "95") (name "unconnected-(U10F-IO{slash}RDN__DIFFIO_RX_R1n_DIFFOUT_R1n-Pad77)") (class "Default")
      (node (ref "U10") (pin "77") (pinfunction "IO/RDN__DIFFIO_RX_R1n_DIFFOUT_R1n_77") (pintype "passive"))
    )
    (net (code "96") (name "unconnected-(U10F-IO{slash}VREFB5N0-Pad81)") (class "Default")
      (node (ref "U10") (pin "81") (pinfunction "IO/VREFB5N0_81") (pintype "passive"))
    )
    (net (code "97") (name "unconnected-(U10G-IO{slash}CLK2n__DIFFIO_RX_R38n_DIFFOUT_R38n-Pad89)") (class "Default")
      (node (ref "U10") (pin "89") (pinfunction "IO/CLK2n__DIFFIO_RX_R38n_DIFFOUT_R38n_89") (pintype "passive"))
    )
    (net (code "98") (name "unconnected-(U10G-IO{slash}DIFFIO_RX_R42n_DIFFOUT_R42n-Pad93)") (class "Default")
      (node (ref "U10") (pin "93") (pinfunction "IO/DIFFIO_RX_R42n_DIFFOUT_R42n_93") (pintype "passive"))
    )
    (net (code "99") (name "unconnected-(U10G-IO{slash}DIFFIO_RX_R51n_DIFFOUT_R51n-Pad101)") (class "Default")
      (node (ref "U10") (pin "101") (pinfunction "IO/DIFFIO_RX_R51n_DIFFOUT_R51n_101") (pintype "passive"))
    )
    (net (code "100") (name "unconnected-(U10G-IO{slash}VREFB6N0-Pad97)") (class "Default")
      (node (ref "U10") (pin "97") (pinfunction "IO/VREFB6N0_97") (pintype "passive"))
    )
    (net (code "101") (name "unconnected-(U10H-IO{slash}VREFB7N0-Pad116)") (class "Default")
      (node (ref "U10") (pin "116") (pinfunction "IO/VREFB7N0_116") (pintype "passive"))
    )
    (net (code "102") (name "unconnected-(U10I-IO-Pad135)") (class "Default")
      (node (ref "U10") (pin "135") (pinfunction "IO_135") (pintype "passive"))
    )
    (net (code "103") (name "unconnected-(U10I-IO{slash}CRC_ERROR_DIFFIO_RX_T48n_DIFFOUT_T48n-Pad134)") (class "Default")
      (node (ref "U10") (pin "134") (pinfunction "IO/CRC_ERROR_DIFFIO_RX_T48n_DIFFOUT_T48n_134") (pintype "passive"))
    )
    (net (code "104") (name "unconnected-(U10I-IO{slash}DEV_OE-Pad125)") (class "Default")
      (node (ref "U10") (pin "125") (pinfunction "IO/DEV_OE_125") (pintype "passive"))
    )
    (net (code "105") (name "unconnected-(U10I-IO{slash}DIFFIO_RX_T45p_DIFFOUT_T45p-Pad127)") (class "Default")
      (node (ref "U10") (pin "127") (pinfunction "IO/DIFFIO_RX_T45p_DIFFOUT_T45p_127") (pintype "passive"))
    )
    (net (code "106") (name "unconnected-(U10I-IO{slash}DIFFIO_RX_T52n_DIFFOUT_T52n_Low_Speed-Pad141)") (class "Default")
      (node (ref "U10") (pin "141") (pinfunction "IO/DIFFIO_RX_T52n_DIFFOUT_T52n_Low_Speed_141") (pintype "passive"))
    )
    (net (code "107") (name "unconnected-(U10I-IO{slash}DIFFIO_RX_T52p_DIFFOUT_T52p-Pad140)") (class "Default")
      (node (ref "U10") (pin "140") (pinfunction "IO/DIFFIO_RX_T52p_DIFFOUT_T52p_140") (pintype "passive"))
    )
    (net (code "108") (name "unconnected-(U10I-IO{slash}VREFB8N0-Pad126)") (class "Default")
      (node (ref "U10") (pin "126") (pinfunction "IO/VREFB8N0_126") (pintype "passive"))
    )
    (net (code "109") (name "unconnected-(U11-NC-Pad1)") (class "Default")
      (node (ref "U11") (pin "1") (pinfunction "NC_1") (pintype "passive+no_connect"))
    )
  )
)
